# esp12carrier_3.net
KiCad netlist of a schematic drawn in EAGLE
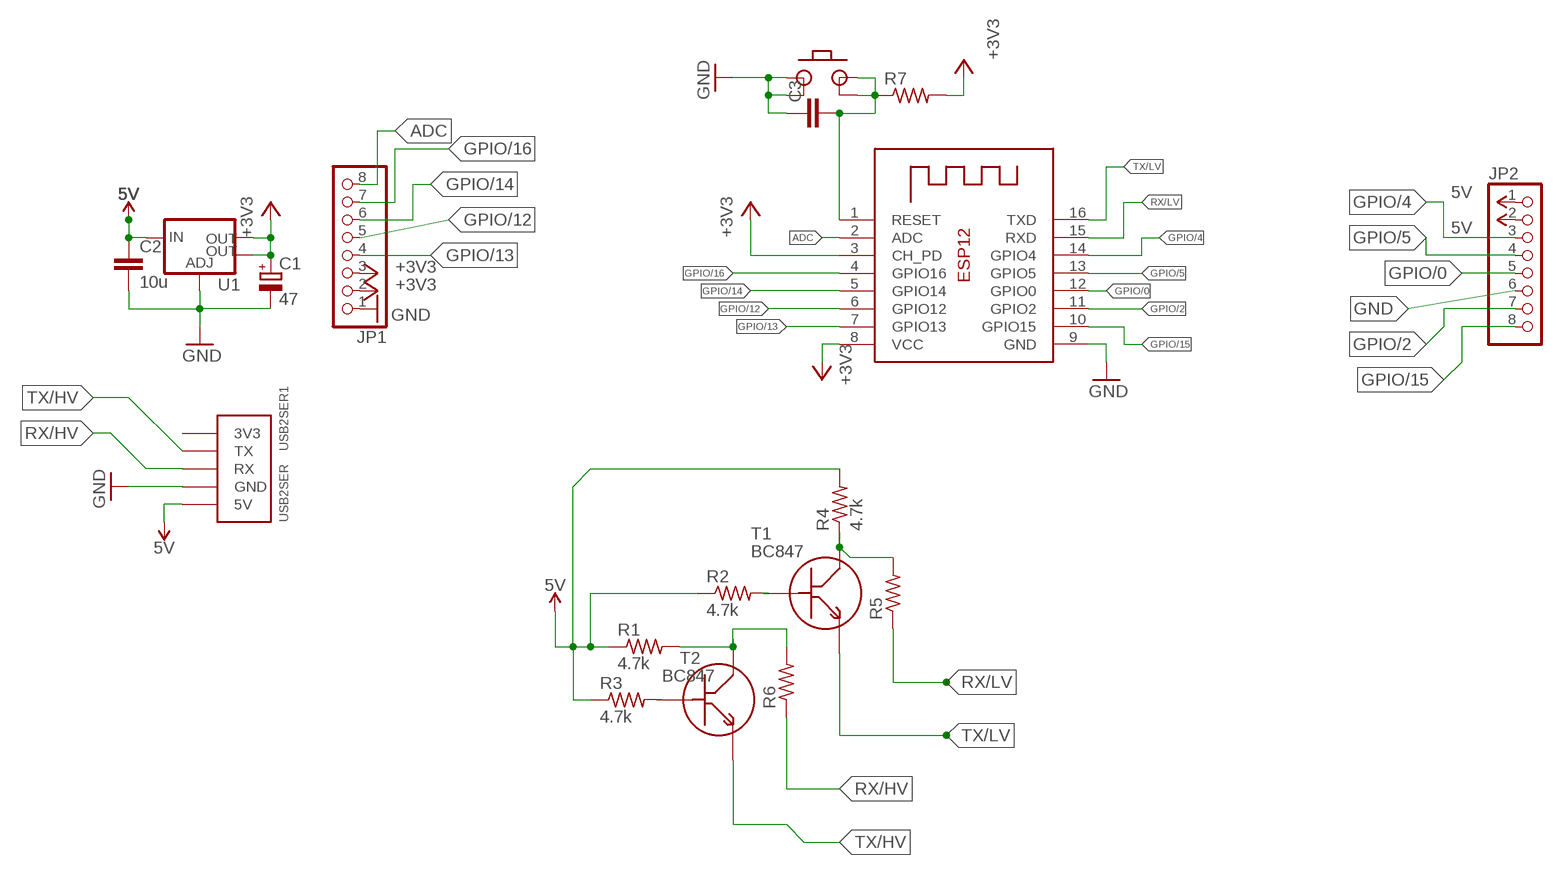
[diagram p0: schematic, sheet 1]

(export (version "E")
  (design (tool "Eeschema 10.0.6"))
  (components
    (comp (ref "C1")
      (value "47")
      (footprint "eagle-import:150CLZ-0810")
      (libsource (lib "eagle-import") (part "CPOL-EU150CLZ-0810"))
    )
    (comp (ref "C2")
      (value "10u")
      (footprint "eagle-import:C0805")
      (libsource (lib "eagle-import") (part "C-EUC0805"))
    )
    (comp (ref "C3")
      (value "C-EUC0805")
      (footprint "eagle-import:C0805")
      (libsource (lib "eagle-import") (part "C-EUC0805"))
    )
    (comp (ref "JP1")
      (value "PINHD-1X8")
      (footprint "eagle-import:1X08")
      (libsource (lib "eagle-import") (part "PINHD-1X8"))
    )
    (comp (ref "JP2")
      (value "PINHD-1X8")
      (footprint "eagle-import:1X08")
      (libsource (lib "eagle-import") (part "PINHD-1X8"))
    )
    (comp (ref "PB1")
      (value "TACTSW")
      (footprint "eagle-import:TACTSW")
      (libsource (lib "eagle-import") (part "TACTSW"))
    )
    (comp (ref "R1")
      (value "4.7k")
      (footprint "eagle-import:M0805")
      (libsource (lib "eagle-import") (part "R-US_M0805"))
    )
    (comp (ref "R2")
      (value "4.7k")
      (footprint "eagle-import:M0805")
      (libsource (lib "eagle-import") (part "R-US_M0805"))
    )
    (comp (ref "R3")
      (value "4.7k")
      (footprint "eagle-import:M0805")
      (libsource (lib "eagle-import") (part "R-US_M0805"))
    )
    (comp (ref "R4")
      (value "4.7k")
      (footprint "eagle-import:M0805")
      (libsource (lib "eagle-import") (part "R-US_M0805"))
    )
    (comp (ref "R5")
      (value "R-US_M0805")
      (footprint "eagle-import:M0805")
      (libsource (lib "eagle-import") (part "R-US_M0805"))
    )
    (comp (ref "R6")
      (value "R-US_M0805")
      (footprint "eagle-import:M0805")
      (libsource (lib "eagle-import") (part "R-US_M0805"))
    )
    (comp (ref "R7")
      (value "R-US_M0805")
      (footprint "eagle-import:M0805")
      (libsource (lib "eagle-import") (part "R-US_M0805"))
    )
    (comp (ref "T1")
      (value "BC847")
      (footprint "eagle-import:BC847")
      (libsource (lib "eagle-import") (part "BC847"))
    )
    (comp (ref "T2")
      (value "BC847")
      (footprint "eagle-import:BC847")
      (libsource (lib "eagle-import") (part "BC847"))
    )
    (comp (ref "U1")
      (value "V_REG_LM1117SOT223")
      (footprint "eagle-import:SOT223")
      (libsource (lib "eagle-import") (part "V_REG_LM1117SOT223"))
    )
    (comp (ref "USB2SER1")
      (value "USB2SER")
      (footprint "eagle-import:USB2SER")
      (libsource (lib "eagle-import") (part "USB2SER"))
    )
    (comp (ref "X2")
      (value "ESP-12")
      (footprint "eagle-import:ESP-12")
      (libsource (lib "eagle-import") (part "ESP-12"))
    )
  )
  (nets
    (net (code "1") (name "+3V3") (class "Default")
      (node (ref "C1") (pin "+") (pinfunction "+_+") (pintype "passive"))
      (node (ref "JP1") (pin "2") (pinfunction "2_2") (pintype "passive"))
      (node (ref "JP1") (pin "3") (pinfunction "3_3") (pintype "passive"))
      (node (ref "R7") (pin "2") (pinfunction "2_2") (pintype "passive"))
      (node (ref "U1") (pin "2") (pinfunction "OUT_2") (pintype "output"))
      (node (ref "U1") (pin "4") (pinfunction "OUT_4") (pintype "output"))
      (node (ref "X2") (pin "3") (pinfunction "CH_PD_3") (pintype "input"))
      (node (ref "X2") (pin "8") (pinfunction "VCC_8") (pintype "power_in"))
    )
    (net (code "2") (name "/3V3") (class "Default")
      (node (ref "USB2SER1") (pin "P$1") (pinfunction "3V3_P$1") (pintype "power_in"))
    )
    (net (code "3") (name "5V") (class "Default")
      (node (ref "C2") (pin "1") (pinfunction "1_1") (pintype "passive"))
      (node (ref "JP2") (pin "1") (pinfunction "1_1") (pintype "passive"))
      (node (ref "JP2") (pin "2") (pinfunction "2_2") (pintype "passive"))
      (node (ref "R1") (pin "1") (pinfunction "1_1") (pintype "passive"))
      (node (ref "R2") (pin "1") (pinfunction "1_1") (pintype "passive"))
      (node (ref "R3") (pin "1") (pinfunction "1_1") (pintype "passive"))
      (node (ref "R4") (pin "2") (pinfunction "2_2") (pintype "passive"))
      (node (ref "U1") (pin "3") (pinfunction "IN_3") (pintype "input"))
      (node (ref "USB2SER1") (pin "P$5") (pinfunction "5V_P$5") (pintype "power_in"))
    )
    (net (code "4") (name "ADC") (class "Default")
      (node (ref "JP1") (pin "8") (pinfunction "8_8") (pintype "passive"))
      (node (ref "X2") (pin "2") (pinfunction "ADC_2") (pintype "passive"))
    )
    (net (code "5") (name "GND") (class "Default")
      (node (ref "C1") (pin "-") (pinfunction "-_-") (pintype "passive"))
      (node (ref "C2") (pin "2") (pinfunction "2_2") (pintype "passive"))
      (node (ref "C3") (pin "1") (pinfunction "1_1") (pintype "passive"))
      (node (ref "JP1") (pin "1") (pinfunction "1_1") (pintype "passive"))
      (node (ref "JP2") (pin "6") (pinfunction "6_6") (pintype "passive"))
      (node (ref "PB1") (pin "P$1") (pinfunction "P$1_P$1") (pintype "passive"))
      (node (ref "PB1") (pin "P$2") (pinfunction "P$3_P$2") (pintype "passive"))
      (node (ref "U1") (pin "1") (pinfunction "ADJ_1") (pintype "input"))
      (node (ref "USB2SER1") (pin "P$4") (pinfunction "GND_P$4") (pintype "power_in"))
      (node (ref "X2") (pin "9") (pinfunction "GND_9") (pintype "power_in"))
    )
    (net (code "6") (name "GPIO{slash}0") (class "Default")
      (node (ref "JP2") (pin "5") (pinfunction "5_5") (pintype "passive"))
      (node (ref "X2") (pin "12") (pinfunction "GPIO0_12") (pintype "bidirectional"))
    )
    (net (code "7") (name "GPIO{slash}2") (class "Default")
      (node (ref "JP2") (pin "7") (pinfunction "7_7") (pintype "passive"))
      (node (ref "X2") (pin "11") (pinfunction "GPIO2_11") (pintype "bidirectional"))
    )
    (net (code "8") (name "GPIO{slash}4") (class "Default")
      (node (ref "JP2") (pin "3") (pinfunction "3_3") (pintype "passive"))
      (node (ref "X2") (pin "14") (pinfunction "GPIO4_14") (pintype "bidirectional"))
    )
    (net (code "9") (name "GPIO{slash}5") (class "Default")
      (node (ref "JP2") (pin "4") (pinfunction "4_4") (pintype "passive"))
      (node (ref "X2") (pin "13") (pinfunction "GPIO5_13") (pintype "bidirectional"))
    )
    (net (code "10") (name "GPIO{slash}12") (class "Default")
      (node (ref "JP1") (pin "5") (pinfunction "5_5") (pintype "passive"))
      (node (ref "X2") (pin "6") (pinfunction "GPIO12_6") (pintype "bidirectional"))
    )
    (net (code "11") (name "GPIO{slash}13") (class "Default")
      (node (ref "JP1") (pin "4") (pinfunction "4_4") (pintype "passive"))
      (node (ref "X2") (pin "7") (pinfunction "GPIO13_7") (pintype "bidirectional"))
    )
    (net (code "12") (name "GPIO{slash}14") (class "Default")
      (node (ref "JP1") (pin "6") (pinfunction "6_6") (pintype "passive"))
      (node (ref "X2") (pin "5") (pinfunction "GPIO14_5") (pintype "bidirectional"))
    )
    (net (code "13") (name "GPIO{slash}15") (class "Default")
      (node (ref "JP2") (pin "8") (pinfunction "8_8") (pintype "passive"))
      (node (ref "X2") (pin "10") (pinfunction "GPIO15_10") (pintype "bidirectional"))
    )
    (net (code "14") (name "GPIO{slash}16") (class "Default")
      (node (ref "JP1") (pin "7") (pinfunction "7_7") (pintype "passive"))
      (node (ref "X2") (pin "4") (pinfunction "GPIO16_4") (pintype "bidirectional"))
    )
    (net (code "15") (name "Net-(PB1-P$2)") (class "Default")
      (node (ref "C3") (pin "2") (pinfunction "2_2") (pintype "passive"))
      (node (ref "PB1") (pin "P$3") (pinfunction "P$2_P$3") (pintype "passive"))
      (node (ref "PB1") (pin "P$4") (pinfunction "P$4_P$4") (pintype "passive"))
      (node (ref "R7") (pin "1") (pinfunction "1_1") (pintype "passive"))
      (node (ref "X2") (pin "1") (pinfunction "RESET_1") (pintype "input"))
    )
    (net (code "16") (name "Net-(T1-B)") (class "Default")
      (node (ref "R2") (pin "2") (pinfunction "2_2") (pintype "passive"))
      (node (ref "T1") (pin "P$2") (pinfunction "B_P$2") (pintype "bidirectional"))
    )
    (net (code "17") (name "Net-(T1-C)") (class "Default")
      (node (ref "R4") (pin "1") (pinfunction "1_1") (pintype "passive"))
      (node (ref "R5") (pin "2") (pinfunction "2_2") (pintype "passive"))
      (node (ref "T1") (pin "P$1") (pinfunction "C_P$1") (pintype "bidirectional"))
    )
    (net (code "18") (name "Net-(T2-B)") (class "Default")
      (node (ref "R3") (pin "2") (pinfunction "2_2") (pintype "passive"))
      (node (ref "T2") (pin "P$2") (pinfunction "B_P$2") (pintype "bidirectional"))
    )
    (net (code "19") (name "Net-(T2-C)") (class "Default")
      (node (ref "R1") (pin "2") (pinfunction "2_2") (pintype "passive"))
      (node (ref "R6") (pin "2") (pinfunction "2_2") (pintype "passive"))
      (node (ref "T2") (pin "P$1") (pinfunction "C_P$1") (pintype "bidirectional"))
    )
    (net (code "20") (name "RX{slash}HV") (class "Default")
      (node (ref "R6") (pin "1") (pinfunction "1_1") (pintype "passive"))
      (node (ref "USB2SER1") (pin "P$3") (pinfunction "RX_P$3") (pintype "bidirectional"))
    )
    (net (code "21") (name "RX{slash}LV") (class "Default")
      (node (ref "R5") (pin "1") (pinfunction "1_1") (pintype "passive"))
      (node (ref "X2") (pin "15") (pinfunction "RXD_15") (pintype "input"))
    )
    (net (code "22") (name "TX{slash}HV") (class "Default")
      (node (ref "T2") (pin "P$3") (pinfunction "E_P$3") (pintype "bidirectional"))
      (node (ref "USB2SER1") (pin "P$2") (pinfunction "TX_P$2") (pintype "bidirectional"))
    )
    (net (code "23") (name "TX{slash}LV") (class "Default")
      (node (ref "T1") (pin "P$3") (pinfunction "E_P$3") (pintype "bidirectional"))
      (node (ref "X2") (pin "16") (pinfunction "TXD_16") (pintype "output"))
    )
  )
)
